# Triggerboard_SOP.net
KiCad netlist of a schematic drawn in EAGLE
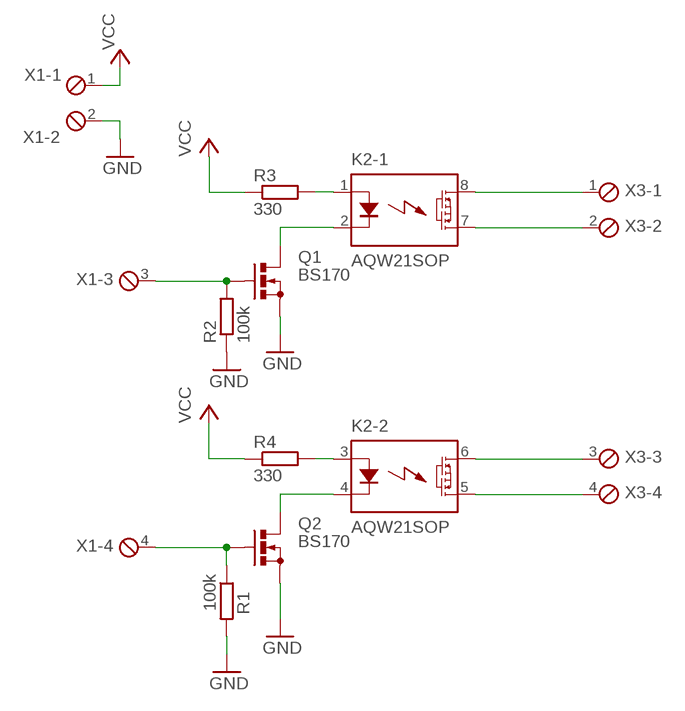
[diagram p0: schematic, sheet 1]

(export (version "E")
  (design (tool "Eeschema 10.0.6"))
  (components
    (comp (ref "K2")
      (value "AQW21SOP")
      (footprint "eagle-import:SOP08")
      (libsource (lib "eagle-import") (part "AQWSOP21"))
    )
    (comp (ref "Q1")
      (value "BS170")
      (footprint "eagle-import:SOT54E")
      (fields (field (name "MF") "ON SEMICONDUCTOR"))
      (libsource (lib "eagle-import") (part "BS170"))
    )
    (comp (ref "Q2")
      (value "BS170")
      (footprint "eagle-import:SOT54E")
      (fields (field (name "MF") "ON SEMICONDUCTOR"))
      (libsource (lib "eagle-import") (part "BS170"))
    )
    (comp (ref "R1")
      (value "100k")
      (footprint "eagle-import:0207_12")
      (libsource (lib "eagle-import") (part "R-EU_0207/12"))
    )
    (comp (ref "R2")
      (value "100k")
      (footprint "eagle-import:0207_12")
      (libsource (lib "eagle-import") (part "R-EU_0207/12"))
    )
    (comp (ref "R3")
      (value "330")
      (footprint "eagle-import:0207_12")
      (fields (field (name "MF") "MULTICOMP PRO") (field (name "MPN") "MCF 1W 330R"))
      (libsource (lib "eagle-import") (part "R-EU_0207/12"))
    )
    (comp (ref "R4")
      (value "330")
      (footprint "eagle-import:0207_12")
      (fields (field (name "MF") "MULTICOMP PRO") (field (name "MPN") "MCF 1W 330R"))
      (libsource (lib "eagle-import") (part "R-EU_0207/12"))
    )
    (comp (ref "X1")
      (value "MPT4")
      (footprint "eagle-import:4POL254")
      (libsource (lib "eagle-import") (part "MPT4"))
    )
    (comp (ref "X3")
      (value "MPT4")
      (footprint "eagle-import:4POL254")
      (libsource (lib "eagle-import") (part "MPT4"))
    )
  )
  (nets
    (net (code "1") (name "GND") (class "Default")
      (node (ref "Q1") (pin "S") (pinfunction "S_S") (pintype "passive"))
      (node (ref "Q2") (pin "S") (pinfunction "S_S") (pintype "passive"))
      (node (ref "R1") (pin "2") (pinfunction "2_2") (pintype "passive"))
      (node (ref "R2") (pin "1") (pinfunction "1_1") (pintype "passive"))
      (node (ref "X1") (pin "2") (pinfunction "1_2") (pintype "passive"))
    )
    (net (code "2") (name "Net-(K2A-A)") (class "Default")
      (node (ref "K2") (pin "1") (pinfunction "A_1") (pintype "passive"))
      (node (ref "R3") (pin "2") (pinfunction "2_2") (pintype "passive"))
    )
    (net (code "3") (name "Net-(K2A-D1)") (class "Default")
      (node (ref "K2") (pin "8") (pinfunction "D1_8") (pintype "passive"))
      (node (ref "X3") (pin "1") (pinfunction "1_1") (pintype "passive"))
    )
    (net (code "4") (name "Net-(K2A-D2)") (class "Default")
      (node (ref "K2") (pin "7") (pinfunction "D2_7") (pintype "passive"))
      (node (ref "X3") (pin "2") (pinfunction "1_2") (pintype "passive"))
    )
    (net (code "5") (name "Net-(K2A-K)") (class "Default")
      (node (ref "K2") (pin "2") (pinfunction "K_2") (pintype "passive"))
      (node (ref "Q1") (pin "D") (pinfunction "D_D") (pintype "passive"))
    )
    (net (code "6") (name "Net-(K2B-A)") (class "Default")
      (node (ref "K2") (pin "3") (pinfunction "A_3") (pintype "passive"))
      (node (ref "R4") (pin "2") (pinfunction "2_2") (pintype "passive"))
    )
    (net (code "7") (name "Net-(K2B-D1)") (class "Default")
      (node (ref "K2") (pin "6") (pinfunction "D1_6") (pintype "passive"))
      (node (ref "X3") (pin "3") (pinfunction "1_3") (pintype "passive"))
    )
    (net (code "8") (name "Net-(K2B-D2)") (class "Default")
      (node (ref "K2") (pin "5") (pinfunction "D2_5") (pintype "passive"))
      (node (ref "X3") (pin "4") (pinfunction "1_4") (pintype "passive"))
    )
    (net (code "9") (name "Net-(K2B-K)") (class "Default")
      (node (ref "K2") (pin "4") (pinfunction "K_4") (pintype "passive"))
      (node (ref "Q2") (pin "D") (pinfunction "D_D") (pintype "passive"))
    )
    (net (code "10") (name "Net-(X1C-1)") (class "Default")
      (node (ref "Q1") (pin "G") (pinfunction "G_G") (pintype "passive"))
      (node (ref "R2") (pin "2") (pinfunction "2_2") (pintype "passive"))
      (node (ref "X1") (pin "3") (pinfunction "1_3") (pintype "passive"))
    )
    (net (code "11") (name "Net-(X1D-1)") (class "Default")
      (node (ref "Q2") (pin "G") (pinfunction "G_G") (pintype "passive"))
      (node (ref "R1") (pin "1") (pinfunction "1_1") (pintype "passive"))
      (node (ref "X1") (pin "4") (pinfunction "1_4") (pintype "passive"))
    )
    (net (code "12") (name "VCC") (class "Default")
      (node (ref "R3") (pin "1") (pinfunction "1_1") (pintype "passive"))
      (node (ref "R4") (pin "1") (pinfunction "1_1") (pintype "passive"))
      (node (ref "X1") (pin "1") (pinfunction "1_1") (pintype "passive"))
    )
  )
)
